# LED_String_AREM-90C0.net
KiCad netlist of a schematic drawn in Altium Designer
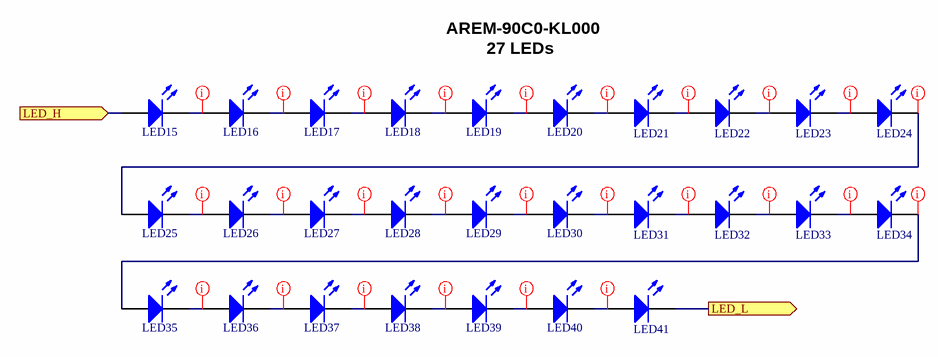
[diagram p0: LED_String_AREM-90C0.SchDoc]

(export (version "E")
  (design (tool "Eeschema 10.0.6"))
  (components
    (comp (ref "LED15")
      (value "AREM-90C0-KL000")
      (footprint "AREM-80C0-LM000")
      (description "Infrared (IR) Emitter 940nm 1.4V 70mA 13.4mW/sr @ 70mA (Typ) 120° 2-PLCC")
      (fields (field (name "MFR") "Broadcom Limited") (field (name "MANUFACTURER") "Broadcom"))
      (libsource (lib "ETHZ Vault") (part "LED"))
    )
    (comp (ref "LED16")
      (value "AREM-90C0-KL000")
      (footprint "AREM-80C0-LM000")
      (description "Infrared (IR) Emitter 940nm 1.4V 70mA 13.4mW/sr @ 70mA (Typ) 120° 2-PLCC")
      (fields (field (name "MFR") "Broadcom Limited") (field (name "MANUFACTURER") "Broadcom"))
      (libsource (lib "ETHZ Vault") (part "LED"))
    )
    (comp (ref "LED17")
      (value "AREM-90C0-KL000")
      (footprint "AREM-80C0-LM000")
      (description "Infrared (IR) Emitter 940nm 1.4V 70mA 13.4mW/sr @ 70mA (Typ) 120° 2-PLCC")
      (fields (field (name "MFR") "Broadcom Limited") (field (name "MANUFACTURER") "Broadcom"))
      (libsource (lib "ETHZ Vault") (part "LED"))
    )
    (comp (ref "LED18")
      (value "AREM-90C0-KL000")
      (footprint "AREM-80C0-LM000")
      (description "Infrared (IR) Emitter 940nm 1.4V 70mA 13.4mW/sr @ 70mA (Typ) 120° 2-PLCC")
      (fields (field (name "MFR") "Broadcom Limited") (field (name "MANUFACTURER") "Broadcom"))
      (libsource (lib "ETHZ Vault") (part "LED"))
    )
    (comp (ref "LED19")
      (value "AREM-90C0-KL000")
      (footprint "AREM-80C0-LM000")
      (description "Infrared (IR) Emitter 940nm 1.4V 70mA 13.4mW/sr @ 70mA (Typ) 120° 2-PLCC")
      (fields (field (name "MFR") "Broadcom Limited") (field (name "MANUFACTURER") "Broadcom"))
      (libsource (lib "ETHZ Vault") (part "LED"))
    )
    (comp (ref "LED20")
      (value "AREM-90C0-KL000")
      (footprint "AREM-80C0-LM000")
      (description "Infrared (IR) Emitter 940nm 1.4V 70mA 13.4mW/sr @ 70mA (Typ) 120° 2-PLCC")
      (fields (field (name "MFR") "Broadcom Limited") (field (name "MANUFACTURER") "Broadcom"))
      (libsource (lib "ETHZ Vault") (part "LED"))
    )
    (comp (ref "LED21")
      (value "AREM-90C0-KL000")
      (footprint "AREM-80C0-LM000")
      (description "Infrared (IR) Emitter 940nm 1.4V 70mA 13.4mW/sr @ 70mA (Typ) 120° 2-PLCC")
      (fields (field (name "MFR") "Broadcom Limited") (field (name "MANUFACTURER") "Broadcom"))
      (libsource (lib "ETHZ Vault") (part "LED"))
    )
    (comp (ref "LED22")
      (value "AREM-90C0-KL000")
      (footprint "AREM-80C0-LM000")
      (description "Infrared (IR) Emitter 940nm 1.4V 70mA 13.4mW/sr @ 70mA (Typ) 120° 2-PLCC")
      (fields (field (name "MFR") "Broadcom Limited") (field (name "MANUFACTURER") "Broadcom"))
      (libsource (lib "ETHZ Vault") (part "LED"))
    )
    (comp (ref "LED23")
      (value "AREM-90C0-KL000")
      (footprint "AREM-80C0-LM000")
      (description "Infrared (IR) Emitter 940nm 1.4V 70mA 13.4mW/sr @ 70mA (Typ) 120° 2-PLCC")
      (fields (field (name "MFR") "Broadcom Limited") (field (name "MANUFACTURER") "Broadcom"))
      (libsource (lib "ETHZ Vault") (part "LED"))
    )
    (comp (ref "LED24")
      (value "AREM-90C0-KL000")
      (footprint "AREM-80C0-LM000")
      (description "Infrared (IR) Emitter 940nm 1.4V 70mA 13.4mW/sr @ 70mA (Typ) 120° 2-PLCC")
      (fields (field (name "MFR") "Broadcom Limited") (field (name "MANUFACTURER") "Broadcom"))
      (libsource (lib "ETHZ Vault") (part "LED"))
    )
    (comp (ref "LED25")
      (value "AREM-90C0-KL000")
      (footprint "AREM-80C0-LM000")
      (description "Infrared (IR) Emitter 940nm 1.4V 70mA 13.4mW/sr @ 70mA (Typ) 120° 2-PLCC")
      (fields (field (name "MFR") "Broadcom Limited") (field (name "MANUFACTURER") "Broadcom"))
      (libsource (lib "ETHZ Vault") (part "LED"))
    )
    (comp (ref "LED26")
      (value "AREM-90C0-KL000")
      (footprint "AREM-80C0-LM000")
      (description "Infrared (IR) Emitter 940nm 1.4V 70mA 13.4mW/sr @ 70mA (Typ) 120° 2-PLCC")
      (fields (field (name "MFR") "Broadcom Limited") (field (name "MANUFACTURER") "Broadcom"))
      (libsource (lib "ETHZ Vault") (part "LED"))
    )
    (comp (ref "LED27")
      (value "AREM-90C0-KL000")
      (footprint "AREM-80C0-LM000")
      (description "Infrared (IR) Emitter 940nm 1.4V 70mA 13.4mW/sr @ 70mA (Typ) 120° 2-PLCC")
      (fields (field (name "MFR") "Broadcom Limited") (field (name "MANUFACTURER") "Broadcom"))
      (libsource (lib "ETHZ Vault") (part "LED"))
    )
    (comp (ref "LED28")
      (value "AREM-90C0-KL000")
      (footprint "AREM-80C0-LM000")
      (description "Infrared (IR) Emitter 940nm 1.4V 70mA 13.4mW/sr @ 70mA (Typ) 120° 2-PLCC")
      (fields (field (name "MFR") "Broadcom Limited") (field (name "MANUFACTURER") "Broadcom"))
      (libsource (lib "ETHZ Vault") (part "LED"))
    )
    (comp (ref "LED29")
      (value "AREM-90C0-KL000")
      (footprint "AREM-80C0-LM000")
      (description "Infrared (IR) Emitter 940nm 1.4V 70mA 13.4mW/sr @ 70mA (Typ) 120° 2-PLCC")
      (fields (field (name "MFR") "Broadcom Limited") (field (name "MANUFACTURER") "Broadcom"))
      (libsource (lib "ETHZ Vault") (part "LED"))
    )
    (comp (ref "LED30")
      (value "AREM-90C0-KL000")
      (footprint "AREM-80C0-LM000")
      (description "Infrared (IR) Emitter 940nm 1.4V 70mA 13.4mW/sr @ 70mA (Typ) 120° 2-PLCC")
      (fields (field (name "MFR") "Broadcom Limited") (field (name "MANUFACTURER") "Broadcom"))
      (libsource (lib "ETHZ Vault") (part "LED"))
    )
    (comp (ref "LED31")
      (value "AREM-90C0-KL000")
      (footprint "AREM-80C0-LM000")
      (description "Infrared (IR) Emitter 940nm 1.4V 70mA 13.4mW/sr @ 70mA (Typ) 120° 2-PLCC")
      (fields (field (name "MFR") "Broadcom Limited") (field (name "MANUFACTURER") "Broadcom"))
      (libsource (lib "ETHZ Vault") (part "LED"))
    )
    (comp (ref "LED32")
      (value "AREM-90C0-KL000")
      (footprint "AREM-80C0-LM000")
      (description "Infrared (IR) Emitter 940nm 1.4V 70mA 13.4mW/sr @ 70mA (Typ) 120° 2-PLCC")
      (fields (field (name "MFR") "Broadcom Limited") (field (name "MANUFACTURER") "Broadcom"))
      (libsource (lib "ETHZ Vault") (part "LED"))
    )
    (comp (ref "LED33")
      (value "AREM-90C0-KL000")
      (footprint "AREM-80C0-LM000")
      (description "Infrared (IR) Emitter 940nm 1.4V 70mA 13.4mW/sr @ 70mA (Typ) 120° 2-PLCC")
      (fields (field (name "MFR") "Broadcom Limited") (field (name "MANUFACTURER") "Broadcom"))
      (libsource (lib "ETHZ Vault") (part "LED"))
    )
    (comp (ref "LED34")
      (value "AREM-90C0-KL000")
      (footprint "AREM-80C0-LM000")
      (description "Infrared (IR) Emitter 940nm 1.4V 70mA 13.4mW/sr @ 70mA (Typ) 120° 2-PLCC")
      (fields (field (name "MFR") "Broadcom Limited") (field (name "MANUFACTURER") "Broadcom"))
      (libsource (lib "ETHZ Vault") (part "LED"))
    )
    (comp (ref "LED35")
      (value "AREM-90C0-KL000")
      (footprint "AREM-80C0-LM000")
      (description "Infrared (IR) Emitter 940nm 1.4V 70mA 13.4mW/sr @ 70mA (Typ) 120° 2-PLCC")
      (fields (field (name "MFR") "Broadcom Limited") (field (name "MANUFACTURER") "Broadcom"))
      (libsource (lib "ETHZ Vault") (part "LED"))
    )
    (comp (ref "LED36")
      (value "AREM-90C0-KL000")
      (footprint "AREM-80C0-LM000")
      (description "Infrared (IR) Emitter 940nm 1.4V 70mA 13.4mW/sr @ 70mA (Typ) 120° 2-PLCC")
      (fields (field (name "MFR") "Broadcom Limited") (field (name "MANUFACTURER") "Broadcom"))
      (libsource (lib "ETHZ Vault") (part "LED"))
    )
    (comp (ref "LED37")
      (value "AREM-90C0-KL000")
      (footprint "AREM-80C0-LM000")
      (description "Infrared (IR) Emitter 940nm 1.4V 70mA 13.4mW/sr @ 70mA (Typ) 120° 2-PLCC")
      (fields (field (name "MFR") "Broadcom Limited") (field (name "MANUFACTURER") "Broadcom"))
      (libsource (lib "ETHZ Vault") (part "LED"))
    )
    (comp (ref "LED38")
      (value "AREM-90C0-KL000")
      (footprint "AREM-80C0-LM000")
      (description "Infrared (IR) Emitter 940nm 1.4V 70mA 13.4mW/sr @ 70mA (Typ) 120° 2-PLCC")
      (fields (field (name "MFR") "Broadcom Limited") (field (name "MANUFACTURER") "Broadcom"))
      (libsource (lib "ETHZ Vault") (part "LED"))
    )
    (comp (ref "LED39")
      (value "AREM-90C0-KL000")
      (footprint "AREM-80C0-LM000")
      (description "Infrared (IR) Emitter 940nm 1.4V 70mA 13.4mW/sr @ 70mA (Typ) 120° 2-PLCC")
      (fields (field (name "MFR") "Broadcom Limited") (field (name "MANUFACTURER") "Broadcom"))
      (libsource (lib "ETHZ Vault") (part "LED"))
    )
    (comp (ref "LED40")
      (value "AREM-90C0-KL000")
      (footprint "AREM-80C0-LM000")
      (description "Infrared (IR) Emitter 940nm 1.4V 70mA 13.4mW/sr @ 70mA (Typ) 120° 2-PLCC")
      (fields (field (name "MFR") "Broadcom Limited") (field (name "MANUFACTURER") "Broadcom"))
      (libsource (lib "ETHZ Vault") (part "LED"))
    )
    (comp (ref "LED41")
      (value "AREM-90C0-KL000")
      (footprint "AREM-80C0-LM000")
      (description "Infrared (IR) Emitter 940nm 1.4V 70mA 13.4mW/sr @ 70mA (Typ) 120° 2-PLCC")
      (fields (field (name "MFR") "Broadcom Limited") (field (name "MANUFACTURER") "Broadcom"))
      (libsource (lib "ETHZ Vault") (part "LED"))
    )
  )
  (nets
    (net (code "1") (name "/LED_H") (class "Default")
      (node (ref "LED15") (pin "2") (pinfunction "A_2") (pintype "passive"))
    )
    (net (code "2") (name "/LED_L") (class "Default")
      (node (ref "LED41") (pin "1") (pinfunction "K_1") (pintype "passive"))
    )
    (net (code "3") (name "Net-(LED15-K)") (class "Default")
      (node (ref "LED15") (pin "1") (pinfunction "K_1") (pintype "passive"))
      (node (ref "LED16") (pin "2") (pinfunction "A_2") (pintype "passive"))
    )
    (net (code "4") (name "Net-(LED16-K)") (class "Default")
      (node (ref "LED16") (pin "1") (pinfunction "K_1") (pintype "passive"))
      (node (ref "LED17") (pin "2") (pinfunction "A_2") (pintype "passive"))
    )
    (net (code "5") (name "Net-(LED17-K)") (class "Default")
      (node (ref "LED17") (pin "1") (pinfunction "K_1") (pintype "passive"))
      (node (ref "LED18") (pin "2") (pinfunction "A_2") (pintype "passive"))
    )
    (net (code "6") (name "Net-(LED18-K)") (class "Default")
      (node (ref "LED18") (pin "1") (pinfunction "K_1") (pintype "passive"))
      (node (ref "LED19") (pin "2") (pinfunction "A_2") (pintype "passive"))
    )
    (net (code "7") (name "Net-(LED19-K)") (class "Default")
      (node (ref "LED19") (pin "1") (pinfunction "K_1") (pintype "passive"))
      (node (ref "LED20") (pin "2") (pinfunction "A_2") (pintype "passive"))
    )
    (net (code "8") (name "Net-(LED20-K)") (class "Default")
      (node (ref "LED20") (pin "1") (pinfunction "K_1") (pintype "passive"))
      (node (ref "LED21") (pin "2") (pinfunction "A_2") (pintype "passive"))
    )
    (net (code "9") (name "Net-(LED21-K)") (class "Default")
      (node (ref "LED21") (pin "1") (pinfunction "K_1") (pintype "passive"))
      (node (ref "LED22") (pin "2") (pinfunction "A_2") (pintype "passive"))
    )
    (net (code "10") (name "Net-(LED22-K)") (class "Default")
      (node (ref "LED22") (pin "1") (pinfunction "K_1") (pintype "passive"))
      (node (ref "LED23") (pin "2") (pinfunction "A_2") (pintype "passive"))
    )
    (net (code "11") (name "Net-(LED23-K)") (class "Default")
      (node (ref "LED23") (pin "1") (pinfunction "K_1") (pintype "passive"))
      (node (ref "LED24") (pin "2") (pinfunction "A_2") (pintype "passive"))
    )
    (net (code "12") (name "Net-(LED24-K)") (class "Default")
      (node (ref "LED24") (pin "1") (pinfunction "K_1") (pintype "passive"))
      (node (ref "LED25") (pin "2") (pinfunction "A_2") (pintype "passive"))
    )
    (net (code "13") (name "Net-(LED25-K)") (class "Default")
      (node (ref "LED25") (pin "1") (pinfunction "K_1") (pintype "passive"))
      (node (ref "LED26") (pin "2") (pinfunction "A_2") (pintype "passive"))
    )
    (net (code "14") (name "Net-(LED26-K)") (class "Default")
      (node (ref "LED26") (pin "1") (pinfunction "K_1") (pintype "passive"))
      (node (ref "LED27") (pin "2") (pinfunction "A_2") (pintype "passive"))
    )
    (net (code "15") (name "Net-(LED27-K)") (class "Default")
      (node (ref "LED27") (pin "1") (pinfunction "K_1") (pintype "passive"))
      (node (ref "LED28") (pin "2") (pinfunction "A_2") (pintype "passive"))
    )
    (net (code "16") (name "Net-(LED28-K)") (class "Default")
      (node (ref "LED28") (pin "1") (pinfunction "K_1") (pintype "passive"))
      (node (ref "LED29") (pin "2") (pinfunction "A_2") (pintype "passive"))
    )
    (net (code "17") (name "Net-(LED29-K)") (class "Default")
      (node (ref "LED29") (pin "1") (pinfunction "K_1") (pintype "passive"))
      (node (ref "LED30") (pin "2") (pinfunction "A_2") (pintype "passive"))
    )
    (net (code "18") (name "Net-(LED30-K)") (class "Default")
      (node (ref "LED30") (pin "1") (pinfunction "K_1") (pintype "passive"))
      (node (ref "LED31") (pin "2") (pinfunction "A_2") (pintype "passive"))
    )
    (net (code "19") (name "Net-(LED31-K)") (class "Default")
      (node (ref "LED31") (pin "1") (pinfunction "K_1") (pintype "passive"))
      (node (ref "LED32") (pin "2") (pinfunction "A_2") (pintype "passive"))
    )
    (net (code "20") (name "Net-(LED32-K)") (class "Default")
      (node (ref "LED32") (pin "1") (pinfunction "K_1") (pintype "passive"))
      (node (ref "LED33") (pin "2") (pinfunction "A_2") (pintype "passive"))
    )
    (net (code "21") (name "Net-(LED33-K)") (class "Default")
      (node (ref "LED33") (pin "1") (pinfunction "K_1") (pintype "passive"))
      (node (ref "LED34") (pin "2") (pinfunction "A_2") (pintype "passive"))
    )
    (net (code "22") (name "Net-(LED34-K)") (class "Default")
      (node (ref "LED34") (pin "1") (pinfunction "K_1") (pintype "passive"))
      (node (ref "LED35") (pin "2") (pinfunction "A_2") (pintype "passive"))
    )
    (net (code "23") (name "Net-(LED35-K)") (class "Default")
      (node (ref "LED35") (pin "1") (pinfunction "K_1") (pintype "passive"))
      (node (ref "LED36") (pin "2") (pinfunction "A_2") (pintype "passive"))
    )
    (net (code "24") (name "Net-(LED36-K)") (class "Default")
      (node (ref "LED36") (pin "1") (pinfunction "K_1") (pintype "passive"))
      (node (ref "LED37") (pin "2") (pinfunction "A_2") (pintype "passive"))
    )
    (net (code "25") (name "Net-(LED37-K)") (class "Default")
      (node (ref "LED37") (pin "1") (pinfunction "K_1") (pintype "passive"))
      (node (ref "LED38") (pin "2") (pinfunction "A_2") (pintype "passive"))
    )
    (net (code "26") (name "Net-(LED38-K)") (class "Default")
      (node (ref "LED38") (pin "1") (pinfunction "K_1") (pintype "passive"))
      (node (ref "LED39") (pin "2") (pinfunction "A_2") (pintype "passive"))
    )
    (net (code "27") (name "Net-(LED39-K)") (class "Default")
      (node (ref "LED39") (pin "1") (pinfunction "K_1") (pintype "passive"))
      (node (ref "LED40") (pin "2") (pinfunction "A_2") (pintype "passive"))
    )
    (net (code "28") (name "Net-(LED40-K)") (class "Default")
      (node (ref "LED40") (pin "1") (pinfunction "K_1") (pintype "passive"))
      (node (ref "LED41") (pin "2") (pinfunction "A_2") (pintype "passive"))
    )
  )
)
